# KGGR_M3.net
KiCad netlist of a schematic drawn in EAGLE
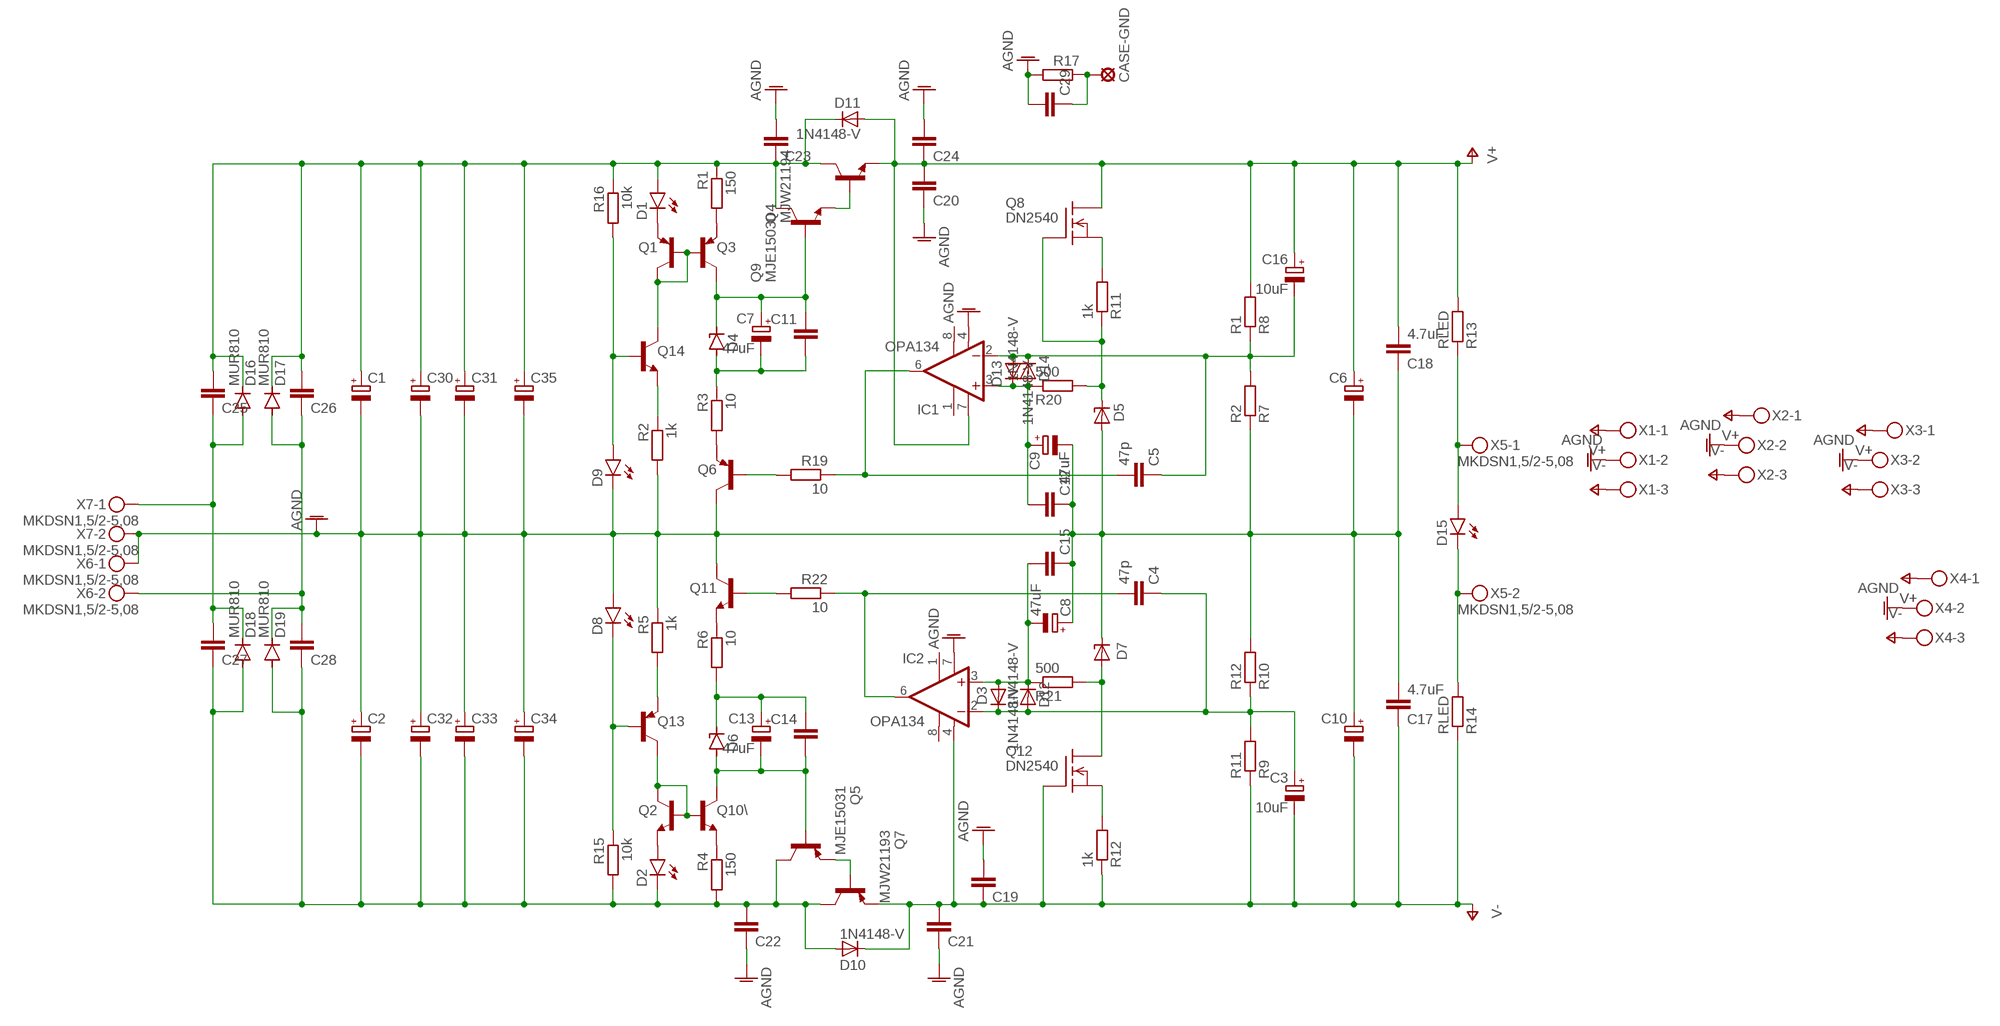
[diagram p0: schematic, sheet 1]

(export (version "E")
  (design (tool "Eeschema 10.0.6"))
  (components
    (comp (ref "C1")
      (value "CPOL-EUE7.5-18")
      (footprint "eagle-import:E7,5-18")
      (libsource (lib "eagle-import") (part "CPOL-EUE7.5-18"))
    )
    (comp (ref "C2")
      (value "CPOL-EUE7.5-18")
      (footprint "eagle-import:E7,5-18")
      (libsource (lib "eagle-import") (part "CPOL-EUE7.5-18"))
    )
    (comp (ref "C3")
      (value "10uF")
      (footprint "eagle-import:E5-8,5")
      (libsource (lib "eagle-import") (part "CPOL-EUE5-8.5"))
    )
    (comp (ref "C4")
      (value "47p")
      (footprint "eagle-import:C025_050-025X075")
      (libsource (lib "eagle-import") (part "C-EU025_050-025X075"))
    )
    (comp (ref "C5")
      (value "47p")
      (footprint "eagle-import:C025_050-025X075")
      (libsource (lib "eagle-import") (part "C-EU025_050-025X075"))
    )
    (comp (ref "C6")
      (value "CPOL-EUE7.5-18")
      (footprint "eagle-import:E7,5-18")
      (libsource (lib "eagle-import") (part "CPOL-EUE7.5-18"))
    )
    (comp (ref "C7")
      (value "47uF")
      (footprint "eagle-import:E5-8,5")
      (libsource (lib "eagle-import") (part "CPOL-EUE5-8.5"))
    )
    (comp (ref "C8")
      (value "47uF")
      (footprint "eagle-import:E5-8,5")
      (libsource (lib "eagle-import") (part "CPOL-EUE5-8.5"))
    )
    (comp (ref "C9")
      (value "47uF")
      (footprint "eagle-import:E5-8,5")
      (libsource (lib "eagle-import") (part "CPOL-EUE5-8.5"))
    )
    (comp (ref "C10")
      (value "CPOL-EUE7.5-18")
      (footprint "eagle-import:E7,5-18")
      (libsource (lib "eagle-import") (part "CPOL-EUE7.5-18"))
    )
    (comp (ref "C11")
      (value "C-EU050-035X075")
      (footprint "eagle-import:C050-035X075")
      (libsource (lib "eagle-import") (part "C-EU050-035X075"))
    )
    (comp (ref "C12")
      (value "C-EU050-035X075")
      (footprint "eagle-import:C050-035X075")
      (libsource (lib "eagle-import") (part "C-EU050-035X075"))
    )
    (comp (ref "C13")
      (value "47uF")
      (footprint "eagle-import:E5-8,5")
      (libsource (lib "eagle-import") (part "CPOL-EUE5-8.5"))
    )
    (comp (ref "C14")
      (value "C-EU050-035X075")
      (footprint "eagle-import:C050-035X075")
      (libsource (lib "eagle-import") (part "C-EU050-035X075"))
    )
    (comp (ref "C15")
      (value "C-EU050-035X075")
      (footprint "eagle-import:C050-035X075")
      (libsource (lib "eagle-import") (part "C-EU050-035X075"))
    )
    (comp (ref "C16")
      (value "10uF")
      (footprint "eagle-import:E5-8,5")
      (libsource (lib "eagle-import") (part "CPOL-EUE5-8.5"))
    )
    (comp (ref "C17")
      (value "4.7uF")
      (footprint "eagle-import:C050-075X075")
      (libsource (lib "eagle-import") (part "C-EU050-075X075"))
    )
    (comp (ref "C18")
      (value "4.7uF")
      (footprint "eagle-import:C050-075X075")
      (libsource (lib "eagle-import") (part "C-EU050-075X075"))
    )
    (comp (ref "C19")
      (value "C-EU050-035X075")
      (footprint "eagle-import:C050-035X075")
      (libsource (lib "eagle-import") (part "C-EU050-035X075"))
    )
    (comp (ref "C20")
      (value "C-EU050-035X075")
      (footprint "eagle-import:C050-035X075")
      (libsource (lib "eagle-import") (part "C-EU050-035X075"))
    )
    (comp (ref "C21")
      (value "C-EU050-035X075")
      (footprint "eagle-import:C050-035X075")
      (libsource (lib "eagle-import") (part "C-EU050-035X075"))
    )
    (comp (ref "C22")
      (value "C-EU050-075X075")
      (footprint "eagle-import:C050-075X075")
      (libsource (lib "eagle-import") (part "C-EU050-075X075"))
    )
    (comp (ref "C23")
      (value "C-EU050-075X075")
      (footprint "eagle-import:C050-075X075")
      (libsource (lib "eagle-import") (part "C-EU050-075X075"))
    )
    (comp (ref "C24")
      (value "C-EU050-035X075")
      (footprint "eagle-import:C050-035X075")
      (libsource (lib "eagle-import") (part "C-EU050-035X075"))
    )
    (comp (ref "C25")
      (value "C-EU050-035X075")
      (footprint "eagle-import:C050-035X075")
      (libsource (lib "eagle-import") (part "C-EU050-035X075"))
    )
    (comp (ref "C26")
      (value "C-EU050-035X075")
      (footprint "eagle-import:C050-035X075")
      (libsource (lib "eagle-import") (part "C-EU050-035X075"))
    )
    (comp (ref "C27")
      (value "C-EU050-035X075")
      (footprint "eagle-import:C050-035X075")
      (libsource (lib "eagle-import") (part "C-EU050-035X075"))
    )
    (comp (ref "C28")
      (value "C-EU050-035X075")
      (footprint "eagle-import:C050-035X075")
      (libsource (lib "eagle-import") (part "C-EU050-035X075"))
    )
    (comp (ref "C29")
      (value "C-EU102_152-062X184")
      (footprint "eagle-import:C102_152-062X184")
      (libsource (lib "eagle-import") (part "C-EU102_152-062X184"))
    )
    (comp (ref "C30")
      (value "CPOL-EUE7.5-18")
      (footprint "eagle-import:E7,5-18")
      (libsource (lib "eagle-import") (part "CPOL-EUE7.5-18"))
    )
    (comp (ref "C31")
      (value "CPOL-EUE7.5-18")
      (footprint "eagle-import:E7,5-18")
      (libsource (lib "eagle-import") (part "CPOL-EUE7.5-18"))
    )
    (comp (ref "C32")
      (value "CPOL-EUE7.5-18")
      (footprint "eagle-import:E7,5-18")
      (libsource (lib "eagle-import") (part "CPOL-EUE7.5-18"))
    )
    (comp (ref "C33")
      (value "CPOL-EUE7.5-18")
      (footprint "eagle-import:E7,5-18")
      (libsource (lib "eagle-import") (part "CPOL-EUE7.5-18"))
    )
    (comp (ref "C34")
      (value "CPOL-EUE7.5-18")
      (footprint "eagle-import:E7,5-18")
      (libsource (lib "eagle-import") (part "CPOL-EUE7.5-18"))
    )
    (comp (ref "C35")
      (value "CPOL-EUE7.5-18")
      (footprint "eagle-import:E7,5-18")
      (libsource (lib "eagle-import") (part "CPOL-EUE7.5-18"))
    )
    (comp (ref "CASE-GND")
      (value "SE14")
      (footprint "eagle-import:SE14")
      (libsource (lib "eagle-import") (part "SE14"))
    )
    (comp (ref "D1")
      (value "LED5MM")
      (footprint "eagle-import:LED5MM")
      (libsource (lib "eagle-import") (part "LED5MM"))
    )
    (comp (ref "D2")
      (value "LED5MM")
      (footprint "eagle-import:LED5MM")
      (libsource (lib "eagle-import") (part "LED5MM"))
    )
    (comp (ref "D3")
      (value "1N4148-V")
      (footprint "eagle-import:1N4148")
      (libsource (lib "eagle-import") (part "1N4148-V"))
    )
    (comp (ref "D4")
      (value "1N4728")
      (footprint "eagle-import:DO41Z10")
      (libsource (lib "eagle-import") (part "1N4728"))
    )
    (comp (ref "D5")
      (value "LT1021")
      (footprint "eagle-import:DIL08")
      (libsource (lib "eagle-import") (part "LT1021-V"))
    )
    (comp (ref "D6")
      (value "1N4728")
      (footprint "eagle-import:DO41Z10")
      (libsource (lib "eagle-import") (part "1N4728"))
    )
    (comp (ref "D7")
      (value "LT1021")
      (footprint "eagle-import:DIL08")
      (libsource (lib "eagle-import") (part "LT1021-V"))
    )
    (comp (ref "D8")
      (value "LED5MM")
      (footprint "eagle-import:LED5MM")
      (libsource (lib "eagle-import") (part "LED5MM"))
    )
    (comp (ref "D9")
      (value "LED5MM")
      (footprint "eagle-import:LED5MM")
      (libsource (lib "eagle-import") (part "LED5MM"))
    )
    (comp (ref "D10")
      (value "1N4148-V")
      (footprint "eagle-import:1N4148")
      (libsource (lib "eagle-import") (part "1N4148-V"))
    )
    (comp (ref "D11")
      (value "1N4148-V")
      (footprint "eagle-import:1N4148")
      (libsource (lib "eagle-import") (part "1N4148-V"))
    )
    (comp (ref "D12")
      (value "1N4148-V")
      (footprint "eagle-import:1N4148")
      (libsource (lib "eagle-import") (part "1N4148-V"))
    )
    (comp (ref "D13")
      (value "1N4148-V")
      (footprint "eagle-import:1N4148")
      (libsource (lib "eagle-import") (part "1N4148-V"))
    )
    (comp (ref "D14")
      (value "1N4148-V")
      (footprint "eagle-import:1N4148")
      (libsource (lib "eagle-import") (part "1N4148-V"))
    )
    (comp (ref "D15")
      (value "LED5MM")
      (footprint "eagle-import:LED5MM")
      (libsource (lib "eagle-import") (part "LED5MM"))
    )
    (comp (ref "D16")
      (value "MUR810")
      (footprint "eagle-import:TO220ACS")
      (libsource (lib "eagle-import") (part "MUR810"))
    )
    (comp (ref "D17")
      (value "MUR810")
      (footprint "eagle-import:TO220ACS")
      (libsource (lib "eagle-import") (part "MUR810"))
    )
    (comp (ref "D18")
      (value "MUR810")
      (footprint "eagle-import:TO220ACS")
      (libsource (lib "eagle-import") (part "MUR810"))
    )
    (comp (ref "D19")
      (value "MUR810")
      (footprint "eagle-import:TO220ACS")
      (libsource (lib "eagle-import") (part "MUR810"))
    )
    (comp (ref "IC1")
      (value "OPA134")
      (footprint "eagle-import:DIL08")
      (fields (field (name "MF") "TEXAS INSTRUMENTS") (field (name "MPN") "OPA134PA"))
      (libsource (lib "eagle-import") (part "OPA134P"))
    )
    (comp (ref "IC2")
      (value "OPA134")
      (footprint "eagle-import:DIL08")
      (fields (field (name "MF") "TEXAS INSTRUMENTS") (field (name "MPN") "OPA134PA"))
      (libsource (lib "eagle-import") (part "OPA134P"))
    )
    (comp (ref "Q1")
      (value "MPSA92-PNP-TO92-EBC")
      (footprint "eagle-import:TO92-EBC")
      (libsource (lib "eagle-import") (part "-PNP-TO92-EBCMPSA92"))
    )
    (comp (ref "Q2")
      (value "MPSA42-NPN-TO92-EBC")
      (footprint "eagle-import:TO92-EBC")
      (libsource (lib "eagle-import") (part "-NPN-TO92-EBCMPSA42"))
    )
    (comp (ref "Q3")
      (value "MPSA92-PNP-TO92-EBC")
      (footprint "eagle-import:TO92-EBC")
      (libsource (lib "eagle-import") (part "-PNP-TO92-EBCMPSA92"))
    )
    (comp (ref "Q4")
      (value "MJW21194")
      (footprint "eagle-import:TO-264")
      (libsource (lib "eagle-import") (part "MJL4281"))
    )
    (comp (ref "Q5")
      (value "MJE15031")
      (footprint "eagle-import:TO220KG")
      (libsource (lib "eagle-import") (part "MJE15031"))
    )
    (comp (ref "Q6")
      (value "MPSA92-PNP-TO92-EBC")
      (footprint "eagle-import:TO92-EBC")
      (libsource (lib "eagle-import") (part "-PNP-TO92-EBCMPSA92"))
    )
    (comp (ref "Q7")
      (value "MJW21193")
      (footprint "eagle-import:TO-264")
      (libsource (lib "eagle-import") (part "MJL4302"))
    )
    (comp (ref "Q8")
      (value "DN2540")
      (footprint "eagle-import:TO92-")
      (libsource (lib "eagle-import") (part "2N7000"))
    )
    (comp (ref "Q9")
      (value "MJE15030")
      (footprint "eagle-import:TO220KG")
      (libsource (lib "eagle-import") (part "MJE15030"))
    )
    (comp (ref "Q10\\")
      (value "MPSA42-NPN-TO92-EBC")
      (footprint "eagle-import:TO92-EBC")
      (libsource (lib "eagle-import") (part "-NPN-TO92-EBCMPSA42"))
    )
    (comp (ref "Q11")
      (value "MPSA42-NPN-TO92-EBC")
      (footprint "eagle-import:TO92-EBC")
      (libsource (lib "eagle-import") (part "-NPN-TO92-EBCMPSA42"))
    )
    (comp (ref "Q12")
      (value "DN2540")
      (footprint "eagle-import:TO92-")
      (libsource (lib "eagle-import") (part "2N7000"))
    )
    (comp (ref "Q13")
      (value "MPSA92-PNP-TO92-EBC")
      (footprint "eagle-import:TO92-EBC")
      (libsource (lib "eagle-import") (part "-PNP-TO92-EBCMPSA92"))
    )
    (comp (ref "Q14")
      (value "MPSA42-NPN-TO92-EBC")
      (footprint "eagle-import:TO92-EBC")
      (libsource (lib "eagle-import") (part "-NPN-TO92-EBCMPSA42"))
    )
    (comp (ref "R1")
      (value "150")
      (footprint "eagle-import:0309_12")
      (libsource (lib "eagle-import") (part "R-EU_0309/12"))
    )
    (comp (ref "R2")
      (value "1k")
      (footprint "eagle-import:0309_12")
      (libsource (lib "eagle-import") (part "R-EU_0309/12"))
    )
    (comp (ref "R3")
      (value "10")
      (footprint "eagle-import:0309_12")
      (libsource (lib "eagle-import") (part "R-EU_0309/12"))
    )
    (comp (ref "R4")
      (value "150")
      (footprint "eagle-import:0309_12")
      (libsource (lib "eagle-import") (part "R-EU_0309/12"))
    )
    (comp (ref "R5")
      (value "1k")
      (footprint "eagle-import:0309_12")
      (libsource (lib "eagle-import") (part "R-EU_0309/12"))
    )
    (comp (ref "R6")
      (value "10")
      (footprint "eagle-import:0309_12")
      (libsource (lib "eagle-import") (part "R-EU_0309/12"))
    )
    (comp (ref "R7")
      (value "R2")
      (footprint "eagle-import:0309_12")
      (libsource (lib "eagle-import") (part "R-EU_0309/12"))
    )
    (comp (ref "R8")
      (value "R1")
      (footprint "eagle-import:0309_12")
      (libsource (lib "eagle-import") (part "R-EU_0309/12"))
    )
    (comp (ref "R9")
      (value "R11")
      (footprint "eagle-import:0309_12")
      (libsource (lib "eagle-import") (part "R-EU_0309/12"))
    )
    (comp (ref "R10")
      (value "R12")
      (footprint "eagle-import:0309_12")
      (libsource (lib "eagle-import") (part "R-EU_0309/12"))
    )
    (comp (ref "R11")
      (value "1k")
      (footprint "eagle-import:0309_12")
      (libsource (lib "eagle-import") (part "R-EU_0309/12"))
    )
    (comp (ref "R12")
      (value "1k")
      (footprint "eagle-import:0309_12")
      (libsource (lib "eagle-import") (part "R-EU_0309/12"))
    )
    (comp (ref "R13")
      (value "RLED")
      (footprint "eagle-import:0309_12")
      (libsource (lib "eagle-import") (part "R-EU_0309/12"))
    )
    (comp (ref "R14")
      (value "RLED")
      (footprint "eagle-import:0309_12")
      (libsource (lib "eagle-import") (part "R-EU_0309/12"))
    )
    (comp (ref "R15")
      (value "10k")
      (footprint "eagle-import:0309_12")
      (libsource (lib "eagle-import") (part "R-EU_0309/12"))
    )
    (comp (ref "R16")
      (value "10k")
      (footprint "eagle-import:0309_12")
      (libsource (lib "eagle-import") (part "R-EU_0309/12"))
    )
    (comp (ref "R17")
      (value "R-EU_0617/22")
      (footprint "eagle-import:0617_22")
      (libsource (lib "eagle-import") (part "R-EU_0617/22"))
    )
    (comp (ref "R19")
      (value "10")
      (footprint "eagle-import:0309_12")
      (libsource (lib "eagle-import") (part "R-EU_0309/12"))
    )
    (comp (ref "R20")
      (value "500")
      (footprint "eagle-import:0309_12")
      (libsource (lib "eagle-import") (part "R-EU_0309/12"))
    )
    (comp (ref "R21")
      (value "500")
      (footprint "eagle-import:0309_12")
      (libsource (lib "eagle-import") (part "R-EU_0309/12"))
    )
    (comp (ref "R22")
      (value "10")
      (footprint "eagle-import:0309_12")
      (libsource (lib "eagle-import") (part "R-EU_0309/12"))
    )
    (comp (ref "X1")
      (value "MKDSN1,5/3-5,08")
      (footprint "eagle-import:MKDSN1,5_3-5,08")
      (libsource (lib "eagle-import") (part "MKDSN1,5/3-5,08"))
    )
    (comp (ref "X2")
      (value "MKDSN1,5/3-5,08")
      (footprint "eagle-import:MKDSN1,5_3-5,08")
      (libsource (lib "eagle-import") (part "MKDSN1,5/3-5,08"))
    )
    (comp (ref "X3")
      (value "MKDSN1,5/3-5,08")
      (footprint "eagle-import:MKDSN1,5_3-5,08")
      (libsource (lib "eagle-import") (part "MKDSN1,5/3-5,08"))
    )
    (comp (ref "X4")
      (value "MKDSN1,5/3-5,08")
      (footprint "eagle-import:MKDSN1,5_3-5,08")
      (libsource (lib "eagle-import") (part "MKDSN1,5/3-5,08"))
    )
    (comp (ref "X5")
      (value "MKDSN1,5/2-5,08")
      (footprint "eagle-import:MKDSN1,5_2-5,08")
      (libsource (lib "eagle-import") (part "MKDSN1,5/2-5,08"))
    )
    (comp (ref "X6")
      (value "MKDSN1,5/2-5,08")
      (footprint "eagle-import:MKDSN1,5_2-5,08")
      (libsource (lib "eagle-import") (part "MKDSN1,5/2-5,08"))
    )
    (comp (ref "X7")
      (value "MKDSN1,5/2-5,08")
      (footprint "eagle-import:MKDSN1,5_2-5,08")
      (libsource (lib "eagle-import") (part "MKDSN1,5/2-5,08"))
    )
  )
  (nets
    (net (code "1") (name "AGND") (class "Default")
      (node (ref "C1") (pin "-") (pinfunction "-_-") (pintype "passive"))
      (node (ref "C10") (pin "+") (pinfunction "+_+") (pintype "passive"))
      (node (ref "C12") (pin "1") (pinfunction "1_1") (pintype "passive"))
      (node (ref "C15") (pin "1") (pinfunction "1_1") (pintype "passive"))
      (node (ref "C17") (pin "2") (pinfunction "2_2") (pintype "passive"))
      (node (ref "C18") (pin "1") (pinfunction "1_1") (pintype "passive"))
      (node (ref "C19") (pin "2") (pinfunction "2_2") (pintype "passive"))
      (node (ref "C2") (pin "+") (pinfunction "+_+") (pintype "passive"))
      (node (ref "C20") (pin "1") (pinfunction "1_1") (pintype "passive"))
      (node (ref "C21") (pin "1") (pinfunction "1_1") (pintype "passive"))
      (node (ref "C22") (pin "1") (pinfunction "1_1") (pintype "passive"))
      (node (ref "C23") (pin "2") (pinfunction "2_2") (pintype "passive"))
      (node (ref "C24") (pin "2") (pinfunction "2_2") (pintype "passive"))
      (node (ref "C29") (pin "2") (pinfunction "2_2") (pintype "passive"))
      (node (ref "C29") (pin "3") (pinfunction "2_3") (pintype "passive"))
      (node (ref "C30") (pin "-") (pinfunction "-_-") (pintype "passive"))
      (node (ref "C31") (pin "-") (pinfunction "-_-") (pintype "passive"))
      (node (ref "C32") (pin "+") (pinfunction "+_+") (pintype "passive"))
      (node (ref "C33") (pin "+") (pinfunction "+_+") (pintype "passive"))
      (node (ref "C34") (pin "+") (pinfunction "+_+") (pintype "passive"))
      (node (ref "C35") (pin "-") (pinfunction "-_-") (pintype "passive"))
      (node (ref "C6") (pin "-") (pinfunction "-_-") (pintype "passive"))
      (node (ref "C8") (pin "+") (pinfunction "+_+") (pintype "passive"))
      (node (ref "C9") (pin "-") (pinfunction "-_-") (pintype "passive"))
      (node (ref "D5") (pin "4") (pinfunction "GND_4") (pintype "passive"))
      (node (ref "D7") (pin "6") (pinfunction "OUT_6") (pintype "passive"))
      (node (ref "D8") (pin "A") (pinfunction "A_A") (pintype "passive"))
      (node (ref "D9") (pin "K") (pinfunction "C_K") (pintype "passive"))
      (node (ref "IC1") (pin "4") (pinfunction "V-_4") (pintype "power_in"))
      (node (ref "IC2") (pin "7") (pinfunction "V+_7") (pintype "power_in"))
      (node (ref "Q11") (pin "C") (pinfunction "C_C") (pintype "passive"))
      (node (ref "Q6") (pin "C") (pinfunction "C_C") (pintype "passive"))
      (node (ref "R10") (pin "2") (pinfunction "2_2") (pintype "passive"))
      (node (ref "R17") (pin "2") (pinfunction "2_2") (pintype "passive"))
      (node (ref "R2") (pin "2") (pinfunction "2_2") (pintype "passive"))
      (node (ref "R5") (pin "1") (pinfunction "1_1") (pintype "passive"))
      (node (ref "R7") (pin "1") (pinfunction "1_1") (pintype "passive"))
      (node (ref "X1") (pin "2") (pinfunction "KL_2") (pintype "passive"))
      (node (ref "X2") (pin "2") (pinfunction "KL_2") (pintype "passive"))
      (node (ref "X3") (pin "2") (pinfunction "KL_2") (pintype "passive"))
      (node (ref "X4") (pin "2") (pinfunction "KL_2") (pintype "passive"))
      (node (ref "X6") (pin "1") (pinfunction "KL_1") (pintype "passive"))
      (node (ref "X7") (pin "2") (pinfunction "KL_2") (pintype "passive"))
    )
    (net (code "2") (name "Net-(C11-Pad2)") (class "Default")
      (node (ref "C11") (pin "2") (pinfunction "2_2") (pintype "passive"))
      (node (ref "C7") (pin "-") (pinfunction "-_-") (pintype "passive"))
      (node (ref "D4") (pin "A") (pinfunction "A_A") (pintype "passive"))
      (node (ref "R3") (pin "1") (pinfunction "1_1") (pintype "passive"))
    )
    (net (code "3") (name "Net-(C13-Pad+)") (class "Default")
      (node (ref "C13") (pin "+") (pinfunction "+_+") (pintype "passive"))
      (node (ref "C14") (pin "1") (pinfunction "1_1") (pintype "passive"))
      (node (ref "D6") (pin "C") (pinfunction "C_C") (pintype "passive"))
      (node (ref "R6") (pin "2") (pinfunction "2_2") (pintype "passive"))
    )
    (net (code "4") (name "Net-(C29-Pad1)") (class "Default")
      (node (ref "C29") (pin "1") (pinfunction "1_1") (pintype "passive"))
      (node (ref "CASE-GND") (pin "MP") (pinfunction "MP_MP") (pintype "passive"))
      (node (ref "R17") (pin "1") (pinfunction "1_1") (pintype "passive"))
    )
    (net (code "5") (name "Net-(D1-C)") (class "Default")
      (node (ref "D1") (pin "K") (pinfunction "C_K") (pintype "passive"))
      (node (ref "Q1") (pin "E") (pinfunction "E_E") (pintype "passive"))
    )
    (net (code "6") (name "Net-(D2-C)") (class "Default")
      (node (ref "C2") (pin "-") (pinfunction "-_-") (pintype "passive"))
      (node (ref "C22") (pin "2") (pinfunction "2_2") (pintype "passive"))
      (node (ref "C27") (pin "1") (pinfunction "1_1") (pintype "passive"))
      (node (ref "C28") (pin "1") (pinfunction "1_1") (pintype "passive"))
      (node (ref "C32") (pin "-") (pinfunction "-_-") (pintype "passive"))
      (node (ref "C33") (pin "-") (pinfunction "-_-") (pintype "passive"))
      (node (ref "C34") (pin "-") (pinfunction "-_-") (pintype "passive"))
      (node (ref "D10") (pin "A") (pinfunction "A_A") (pintype "passive"))
      (node (ref "D18") (pin "A") (pinfunction "A_A") (pintype "passive"))
      (node (ref "D19") (pin "A") (pinfunction "A_A") (pintype "passive"))
      (node (ref "D2") (pin "K") (pinfunction "C_K") (pintype "passive"))
      (node (ref "Q5") (pin "2") (pinfunction "C_2") (pintype "passive"))
      (node (ref "Q7") (pin "C") (pinfunction "C_C") (pintype "passive"))
      (node (ref "R15") (pin "2") (pinfunction "2_2") (pintype "passive"))
      (node (ref "R4") (pin "2") (pinfunction "2_2") (pintype "passive"))
    )
    (net (code "7") (name "Net-(D2-PadA)") (class "Default")
      (node (ref "D2") (pin "A") (pinfunction "A_A") (pintype "passive"))
      (node (ref "Q2") (pin "E") (pinfunction "E_E") (pintype "passive"))
    )
    (net (code "8") (name "Net-(D5-OUT)") (class "Default")
      (node (ref "D5") (pin "6") (pinfunction "OUT_6") (pintype "passive"))
      (node (ref "Q8") (pin "2") (pinfunction "G_2") (pintype "passive"))
      (node (ref "R11") (pin "1") (pinfunction "1_1") (pintype "passive"))
      (node (ref "R20") (pin "2") (pinfunction "2_2") (pintype "passive"))
    )
    (net (code "9") (name "Net-(D7-GND)") (class "Default")
      (node (ref "D7") (pin "4") (pinfunction "GND_4") (pintype "passive"))
      (node (ref "Q12") (pin "1") (pinfunction "D_1") (pintype "passive"))
      (node (ref "R21") (pin "2") (pinfunction "2_2") (pintype "passive"))
    )
    (net (code "10") (name "Net-(D8-C)") (class "Default")
      (node (ref "D8") (pin "K") (pinfunction "C_K") (pintype "passive"))
      (node (ref "Q13") (pin "B") (pinfunction "B_B") (pintype "passive"))
      (node (ref "R15") (pin "1") (pinfunction "1_1") (pintype "passive"))
    )
    (net (code "11") (name "Net-(D9-PadA)") (class "Default")
      (node (ref "D9") (pin "A") (pinfunction "A_A") (pintype "passive"))
      (node (ref "Q14") (pin "B") (pinfunction "B_B") (pintype "passive"))
      (node (ref "R16") (pin "2") (pinfunction "2_2") (pintype "passive"))
    )
    (net (code "12") (name "Net-(D15-C)") (class "Default")
      (node (ref "D15") (pin "K") (pinfunction "C_K") (pintype "passive"))
      (node (ref "R14") (pin "2") (pinfunction "2_2") (pintype "passive"))
      (node (ref "X5") (pin "2") (pinfunction "KL_2") (pintype "passive"))
    )
    (net (code "13") (name "Net-(IC1-+IN)") (class "Default")
      (node (ref "C12") (pin "2") (pinfunction "2_2") (pintype "passive"))
      (node (ref "C9") (pin "+") (pinfunction "+_+") (pintype "passive"))
      (node (ref "D13") (pin "C") (pinfunction "C_C") (pintype "passive"))
      (node (ref "D14") (pin "A") (pinfunction "A_A") (pintype "passive"))
      (node (ref "IC1") (pin "3") (pinfunction "+IN_3") (pintype "input"))
      (node (ref "R20") (pin "1") (pinfunction "1_1") (pintype "passive"))
    )
    (net (code "14") (name "Net-(IC1--IN)") (class "Default")
      (node (ref "C16") (pin "-") (pinfunction "-_-") (pintype "passive"))
      (node (ref "C5") (pin "1") (pinfunction "1_1") (pintype "passive"))
      (node (ref "D13") (pin "A") (pinfunction "A_A") (pintype "passive"))
      (node (ref "D14") (pin "C") (pinfunction "C_C") (pintype "passive"))
      (node (ref "IC1") (pin "2") (pinfunction "-IN_2") (pintype "input"))
      (node (ref "R7") (pin "2") (pinfunction "2_2") (pintype "passive"))
      (node (ref "R8") (pin "1") (pinfunction "1_1") (pintype "passive"))
    )
    (net (code "15") (name "Net-(IC1-OUT)") (class "Default")
      (node (ref "C5") (pin "2") (pinfunction "2_2") (pintype "passive"))
      (node (ref "C5") (pin "3") (pinfunction "2_3") (pintype "passive"))
      (node (ref "IC1") (pin "6") (pinfunction "OUT_6") (pintype "output"))
      (node (ref "R19") (pin "1") (pinfunction "1_1") (pintype "passive"))
    )
    (net (code "16") (name "Net-(IC2-+IN)") (class "Default")
      (node (ref "C15") (pin "2") (pinfunction "2_2") (pintype "passive"))
      (node (ref "C8") (pin "-") (pinfunction "-_-") (pintype "passive"))
      (node (ref "D12") (pin "C") (pinfunction "C_C") (pintype "passive"))
      (node (ref "D3") (pin "A") (pinfunction "A_A") (pintype "passive"))
      (node (ref "IC2") (pin "3") (pinfunction "+IN_3") (pintype "input"))
      (node (ref "R21") (pin "1") (pinfunction "1_1") (pintype "passive"))
    )
    (net (code "17") (name "Net-(IC2--IN)") (class "Default")
      (node (ref "C3") (pin "+") (pinfunction "+_+") (pintype "passive"))
      (node (ref "C4") (pin "1") (pinfunction "1_1") (pintype "passive"))
      (node (ref "D12") (pin "A") (pinfunction "A_A") (pintype "passive"))
      (node (ref "D3") (pin "C") (pinfunction "C_C") (pintype "passive"))
      (node (ref "IC2") (pin "2") (pinfunction "-IN_2") (pintype "input"))
      (node (ref "R10") (pin "1") (pinfunction "1_1") (pintype "passive"))
      (node (ref "R9") (pin "2") (pinfunction "2_2") (pintype "passive"))
    )
    (net (code "18") (name "Net-(IC2-OUT)") (class "Default")
      (node (ref "C4") (pin "2") (pinfunction "2_2") (pintype "passive"))
      (node (ref "C4") (pin "3") (pinfunction "2_3") (pintype "passive"))
      (node (ref "IC2") (pin "6") (pinfunction "OUT_6") (pintype "output"))
      (node (ref "R22") (pin "1") (pinfunction "1_1") (pintype "passive"))
    )
    (net (code "19") (name "Net-(Q1-PadB)") (class "Default")
      (node (ref "Q1") (pin "B") (pinfunction "B_B") (pintype "passive"))
      (node (ref "Q1") (pin "C") (pinfunction "C_C") (pintype "passive"))
      (node (ref "Q14") (pin "C") (pinfunction "C_C") (pintype "passive"))
      (node (ref "Q3") (pin "B") (pinfunction "B_B") (pintype "passive"))
    )
    (net (code "20") (name "Net-(Q3-PadE)") (class "Default")
      (node (ref "Q3") (pin "E") (pinfunction "E_E") (pintype "passive"))
      (node (ref "R1") (pin "2") (pinfunction "2_2") (pintype "passive"))
    )
    (net (code "21") (name "Net-(Q5-B)") (class "Default")
      (node (ref "C13") (pin "-") (pinfunction "-_-") (pintype "passive"))
      (node (ref "C14") (pin "2") (pinfunction "2_2") (pintype "passive"))
      (node (ref "D6") (pin "A") (pinfunction "A_A") (pintype "passive"))
      (node (ref "Q10\\") (pin "C") (pinfunction "C_C") (pintype "passive"))
      (node (ref "Q5") (pin "1") (pinfunction "B_1") (pintype "passive"))
    )
    (net (code "22") (name "Net-(Q5-E)") (class "Default")
      (node (ref "Q5") (pin "3") (pinfunction "E_3") (pintype "passive"))
      (node (ref "Q7") (pin "B") (pinfunction "B_B") (pintype "passive"))
    )
    (net (code "23") (name "Net-(Q6-PadB)") (class "Default")
      (node (ref "Q6") (pin "B") (pinfunction "B_B") (pintype "passive"))
      (node (ref "R19") (pin "2") (pinfunction "2_2") (pintype "passive"))
    )
    (net (code "24") (name "Net-(Q6-PadE)") (class "Default")
      (node (ref "Q6") (pin "E") (pinfunction "E_E") (pintype "passive"))
      (node (ref "R3") (pin "2") (pinfunction "2_2") (pintype "passive"))
    )
    (net (code "25") (name "Net-(Q8-S)") (class "Default")
      (node (ref "Q8") (pin "3") (pinfunction "S_3") (pintype "passive"))
      (node (ref "R11") (pin "2") (pinfunction "2_2") (pintype "passive"))
    )
    (net (code "26") (name "Net-(Q9-B)") (class "Default")
      (node (ref "C11") (pin "1") (pinfunction "1_1") (pintype "passive"))
      (node (ref "C7") (pin "+") (pinfunction "+_+") (pintype "passive"))
      (node (ref "D4") (pin "C") (pinfunction "C_C") (pintype "passive"))
      (node (ref "Q3") (pin "C") (pinfunction "C_C") (pintype "passive"))
      (node (ref "Q9") (pin "1") (pinfunction "B_1") (pintype "passive"))
    )
    (net (code "27") (name "Net-(Q9-C)") (class "Default")
      (node (ref "C1") (pin "+") (pinfunction "+_+") (pintype "passive"))
      (node (ref "C23") (pin "1") (pinfunction "1_1") (pintype "passive"))
      (node (ref "C25") (pin "2") (pinfunction "2_2") (pintype "passive"))
      (node (ref "C26") (pin "2") (pinfunction "2_2") (pintype "passive"))
      (node (ref "C30") (pin "+") (pinfunction "+_+") (pintype "passive"))
      (node (ref "C31") (pin "+") (pinfunction "+_+") (pintype "passive"))
      (node (ref "C35") (pin "+") (pinfunction "+_+") (pintype "passive"))
      (node (ref "D1") (pin "A") (pinfunction "A_A") (pintype "passive"))
      (node (ref "D11") (pin "C") (pinfunction "C_C") (pintype "passive"))
      (node (ref "D16") (pin "C") (pinfunction "C_C") (pintype "passive"))
      (node (ref "D17") (pin "C") (pinfunction "C_C") (pintype "passive"))
      (node (ref "Q4") (pin "C") (pinfunction "C_C") (pintype "passive"))
      (node (ref "Q9") (pin "2") (pinfunction "C_2") (pintype "passive"))
      (node (ref "R1") (pin "1") (pinfunction "1_1") (pintype "passive"))
      (node (ref "R16") (pin "1") (pinfunction "1_1") (pintype "passive"))
    )
    (net (code "28") (name "Net-(Q9-E)") (class "Default")
      (node (ref "Q4") (pin "B") (pinfunction "B_B") (pintype "passive"))
      (node (ref "Q9") (pin "3") (pinfunction "E_3") (pintype "passive"))
    )
    (net (code "29") (name "Net-(Q10\\-PadB)") (class "Default")
      (node (ref "Q10\\") (pin "B") (pinfunction "B_B") (pintype "passive"))
      (node (ref "Q13") (pin "C") (pinfunction "C_C") (pintype "passive"))
      (node (ref "Q2") (pin "B") (pinfunction "B_B") (pintype "passive"))
      (node (ref "Q2") (pin "C") (pinfunction "C_C") (pintype "passive"))
    )
    (net (code "30") (name "Net-(Q10\\-PadE)") (class "Default")
      (node (ref "Q10\\") (pin "E") (pinfunction "E_E") (pintype "passive"))
      (node (ref "R4") (pin "1") (pinfunction "1_1") (pintype "passive"))
    )
    (net (code "31") (name "Net-(Q11-PadB)") (class "Default")
      (node (ref "Q11") (pin "B") (pinfunction "B_B") (pintype "passive"))
      (node (ref "R22") (pin "2") (pinfunction "2_2") (pintype "passive"))
    )
    (net (code "32") (name "Net-(Q11-PadE)") (class "Default")
      (node (ref "Q11") (pin "E") (pinfunction "E_E") (pintype "passive"))
      (node (ref "R6") (pin "1") (pinfunction "1_1") (pintype "passive"))
    )
    (net (code "33") (name "Net-(Q12-S)") (class "Default")
      (node (ref "Q12") (pin "3") (pinfunction "S_3") (pintype "passive"))
      (node (ref "R12") (pin "2") (pinfunction "2_2") (pintype "passive"))
    )
    (net (code "34") (name "Net-(Q13-PadE)") (class "Default")
      (node (ref "Q13") (pin "E") (pinfunction "E_E") (pintype "passive"))
      (node (ref "R5") (pin "2") (pinfunction "2_2") (pintype "passive"))
    )
    (net (code "35") (name "Net-(Q14-PadE)") (class "Default")
      (node (ref "Q14") (pin "E") (pinfunction "E_E") (pintype "passive"))
      (node (ref "R2") (pin "1") (pinfunction "1_1") (pintype "passive"))
    )
    (net (code "36") (name "Net-(X5A-KL)") (class "Default")
      (node (ref "D15") (pin "A") (pinfunction "A_A") (pintype "passive"))
      (node (ref "R13") (pin "1") (pinfunction "1_1") (pintype "passive"))
      (node (ref "X5") (pin "1") (pinfunction "KL_1") (pintype "passive"))
    )
    (net (code "37") (name "Net-(X6B-KL)") (class "Default")
      (node (ref "C26") (pin "1") (pinfunction "1_1") (pintype "passive"))
      (node (ref "C28") (pin "2") (pinfunction "2_2") (pintype "passive"))
      (node (ref "D17") (pin "A") (pinfunction "A_A") (pintype "passive"))
      (node (ref "D19") (pin "C") (pinfunction "C_C") (pintype "passive"))
      (node (ref "X6") (pin "2") (pinfunction "KL_2") (pintype "passive"))
    )
    (net (code "38") (name "Net-(X7A-KL)") (class "Default")
      (node (ref "C25") (pin "1") (pinfunction "1_1") (pintype "passive"))
      (node (ref "C27") (pin "2") (pinfunction "2_2") (pintype "passive"))
      (node (ref "D16") (pin "A") (pinfunction "A_A") (pintype "passive"))
      (node (ref "D18") (pin "C") (pinfunction "C_C") (pintype "passive"))
      (node (ref "X7") (pin "1") (pinfunction "KL_1") (pintype "passive"))
    )
    (net (code "39") (name "V+") (class "Default")
      (node (ref "C16") (pin "+") (pinfunction "+_+") (pintype "passive"))
      (node (ref "C18") (pin "2") (pinfunction "2_2") (pintype "passive"))
      (node (ref "C20") (pin "2") (pinfunction "2_2") (pintype "passive"))
      (node (ref "C24") (pin "1") (pinfunction "1_1") (pintype "passive"))
      (node (ref "C6") (pin "+") (pinfunction "+_+") (pintype "passive"))
      (node (ref "D11") (pin "A") (pinfunction "A_A") (pintype "passive"))
      (node (ref "IC1") (pin "7") (pinfunction "V+_7") (pintype "power_in"))
      (node (ref "Q4") (pin "E") (pinfunction "E_E") (pintype "passive"))
      (node (ref "Q8") (pin "1") (pinfunction "D_1") (pintype "passive"))
      (node (ref "R13") (pin "2") (pinfunction "2_2") (pintype "passive"))
      (node (ref "R8") (pin "2") (pinfunction "2_2") (pintype "passive"))
      (node (ref "X1") (pin "1") (pinfunction "KL_1") (pintype "passive"))
      (node (ref "X2") (pin "1") (pinfunction "KL_1") (pintype "passive"))
      (node (ref "X3") (pin "1") (pinfunction "KL_1") (pintype "passive"))
      (node (ref "X4") (pin "1") (pinfunction "KL_1") (pintype "passive"))
    )
    (net (code "40") (name "V-") (class "Default")
      (node (ref "C10") (pin "-") (pinfunction "-_-") (pintype "passive"))
      (node (ref "C17") (pin "1") (pinfunction "1_1") (pintype "passive"))
      (node (ref "C19") (pin "1") (pinfunction "1_1") (pintype "passive"))
      (node (ref "C21") (pin "2") (pinfunction "2_2") (pintype "passive"))
      (node (ref "C3") (pin "-") (pinfunction "-_-") (pintype "passive"))
      (node (ref "D10") (pin "C") (pinfunction "C_C") (pintype "passive"))
      (node (ref "IC2") (pin "4") (pinfunction "V-_4") (pintype "power_in"))
      (node (ref "Q12") (pin "2") (pinfunction "G_2") (pintype "passive"))
      (node (ref "Q7") (pin "E") (pinfunction "E_E") (pintype "passive"))
      (node (ref "R12") (pin "1") (pinfunction "1_1") (pintype "passive"))
      (node (ref "R14") (pin "1") (pinfunction "1_1") (pintype "passive"))
      (node (ref "R9") (pin "1") (pinfunction "1_1") (pintype "passive"))
      (node (ref "X1") (pin "3") (pinfunction "KL_3") (pintype "passive"))
      (node (ref "X2") (pin "3") (pinfunction "KL_3") (pintype "passive"))
      (node (ref "X3") (pin "3") (pinfunction "KL_3") (pintype "passive"))
      (node (ref "X4") (pin "3") (pinfunction "KL_3") (pintype "passive"))
    )
    (net (code "41") (name "unconnected-(IC1-TRIM1-Pad1)") (class "Default")
      (node (ref "IC1") (pin "1") (pinfunction "TRIM1_1") (pintype "passive"))
    )
    (net (code "42") (name "unconnected-(IC1-TRIM2-Pad8)") (class "Default")
      (node (ref "IC1") (pin "8") (pinfunction "TRIM2_8") (pintype "passive"))
    )
    (net (code "43") (name "unconnected-(IC2-TRIM1-Pad1)") (class "Default")
      (node (ref "IC2") (pin "1") (pinfunction "TRIM1_1") (pintype "passive"))
    )
    (net (code "44") (name "unconnected-(IC2-TRIM2-Pad8)") (class "Default")
      (node (ref "IC2") (pin "8") (pinfunction "TRIM2_8") (pintype "passive"))
    )
  )
)
